# MYO_Ganglion_no_usb.net
KiCad netlist of a schematic drawn in EAGLE
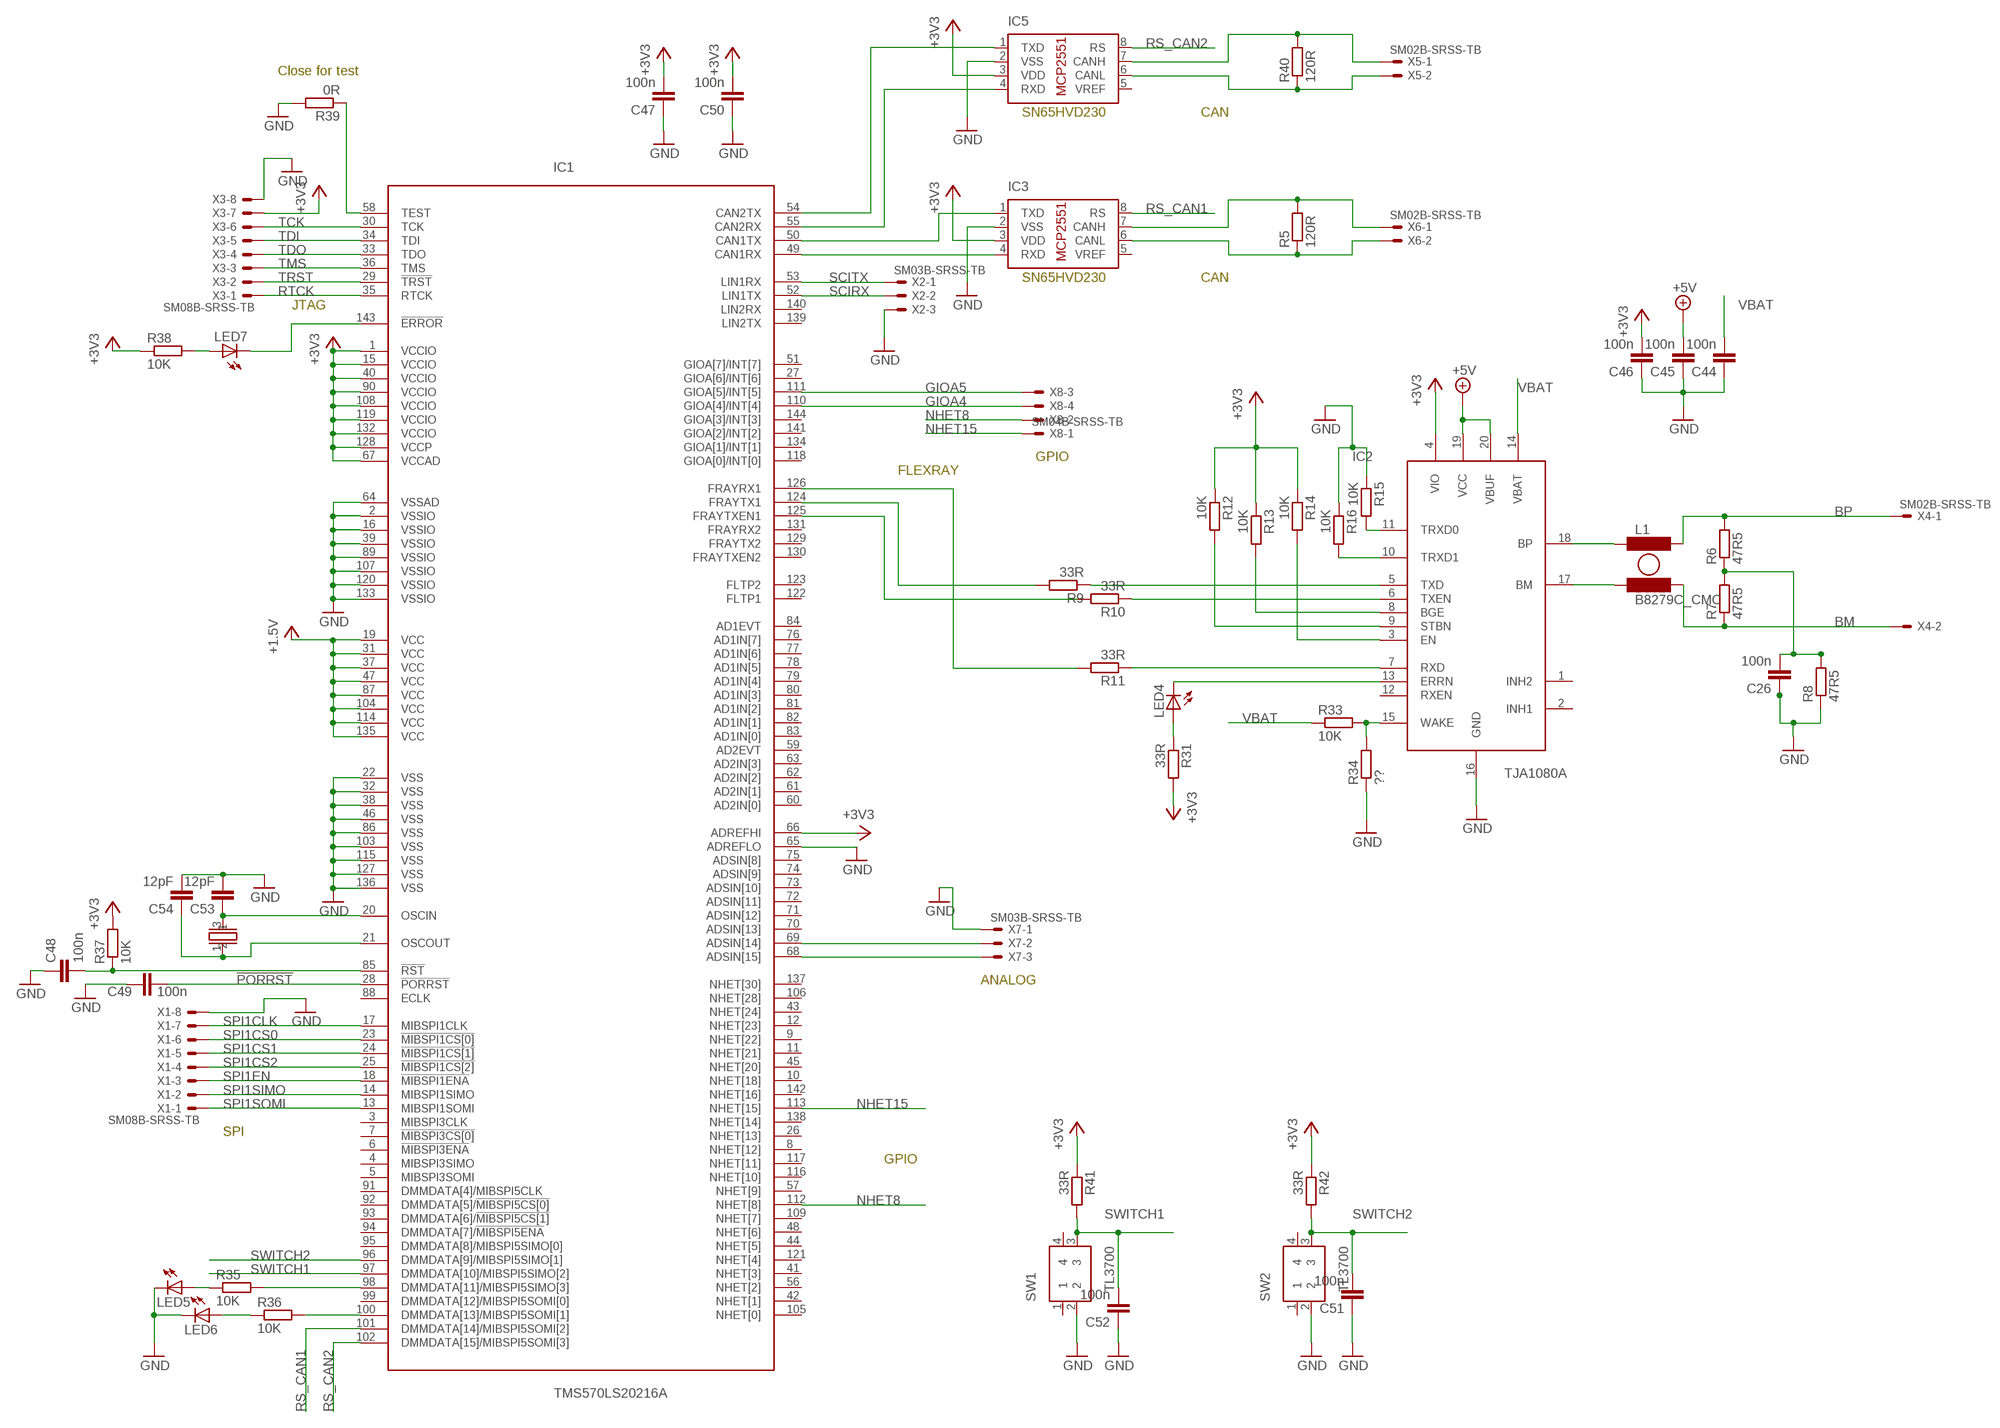
[diagram p0: schematic, sheet 1]
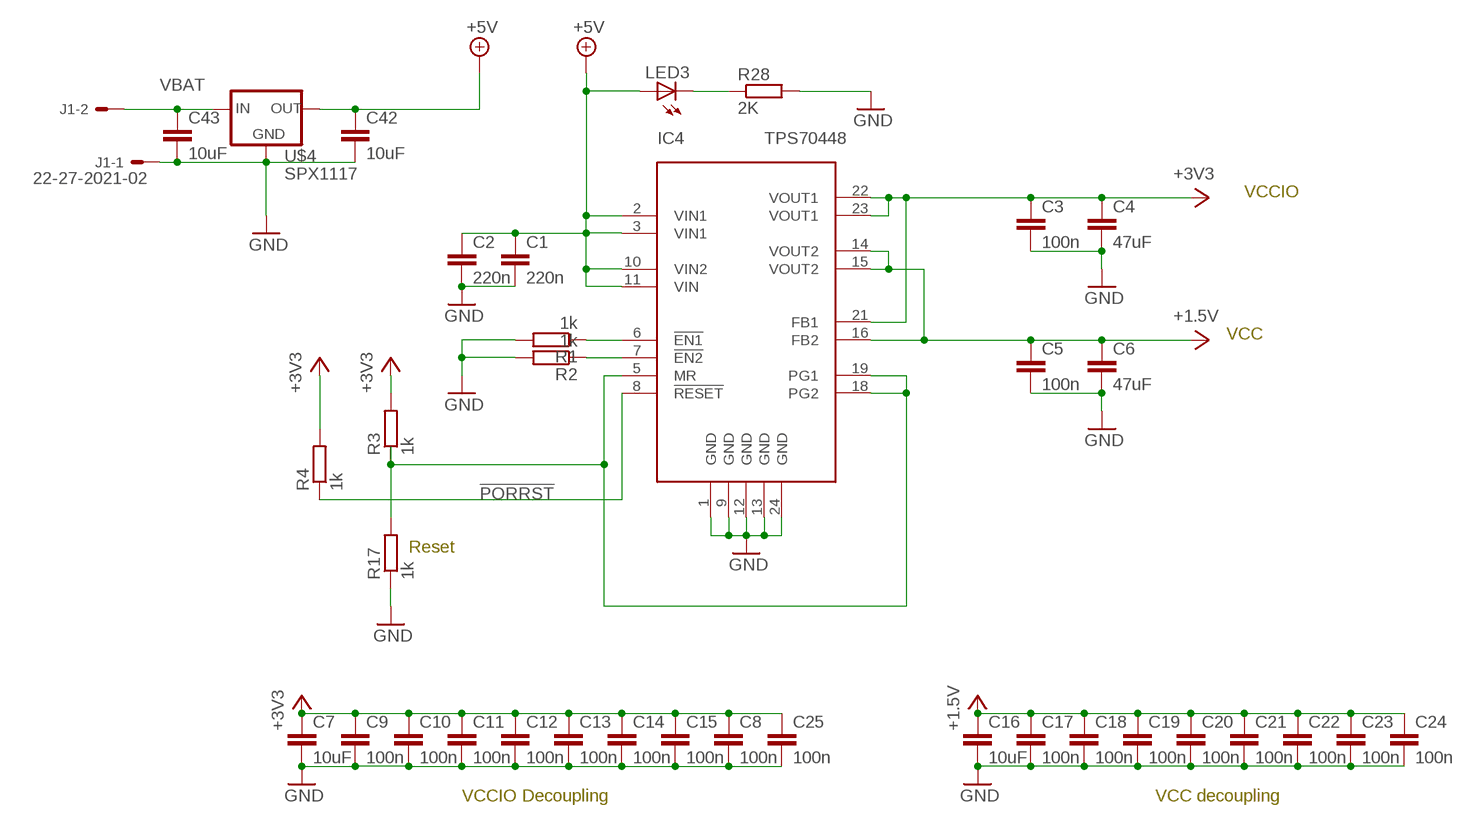
[diagram p1: schematic, sheet 2]

(export (version "E")
  (design (tool "Eeschema 10.0.6"))
  (components
    (comp (ref "C26")
      (value "100n")
      (footprint "eagle-import:C0402K")
      (libsource (lib "eagle-import") (part "C-EUC0402K"))
    )
    (comp (ref "C44")
      (value "100n")
      (footprint "eagle-import:C0402K")
      (libsource (lib "eagle-import") (part "C-EUC0402K"))
    )
    (comp (ref "C45")
      (value "100n")
      (footprint "eagle-import:C0402K")
      (libsource (lib "eagle-import") (part "C-EUC0402K"))
    )
    (comp (ref "C46")
      (value "100n")
      (footprint "eagle-import:C0402K")
      (libsource (lib "eagle-import") (part "C-EUC0402K"))
    )
    (comp (ref "C47")
      (value "100n")
      (footprint "eagle-import:C0402K")
      (libsource (lib "eagle-import") (part "C-EUC0402K"))
    )
    (comp (ref "C48")
      (value "100n")
      (footprint "eagle-import:C0402K")
      (libsource (lib "eagle-import") (part "C-EUC0402K"))
    )
    (comp (ref "C49")
      (value "100n")
      (footprint "eagle-import:C0402K")
      (libsource (lib "eagle-import") (part "C-EUC0402K"))
    )
    (comp (ref "C50")
      (value "100n")
      (footprint "eagle-import:C0402K")
      (libsource (lib "eagle-import") (part "C-EUC0402K"))
    )
    (comp (ref "C51")
      (value "100n")
      (footprint "eagle-import:C0402K")
      (libsource (lib "eagle-import") (part "C-EUC0402K"))
    )
    (comp (ref "C52")
      (value "100n")
      (footprint "eagle-import:C0402K")
      (libsource (lib "eagle-import") (part "C-EUC0402K"))
    )
    (comp (ref "C53")
      (value "12pF")
      (footprint "eagle-import:C0402K")
      (libsource (lib "eagle-import") (part "C-EUC0402K"))
    )
    (comp (ref "C54")
      (value "12pF")
      (footprint "eagle-import:C0402K")
      (libsource (lib "eagle-import") (part "C-EUC0402K"))
    )
    (comp (ref "IC1")
      (value "TMS570LS20216A")
      (footprint "eagle-import:PQFP144")
      (libsource (lib "eagle-import") (part "TMS570LS20216A"))
    )
    (comp (ref "IC2")
      (value "TJA1080A")
      (footprint "eagle-import:TSSOP20")
      (libsource (lib "eagle-import") (part "TJA1080A"))
    )
    (comp (ref "IC3")
      (value "MCP2551/SN")
      (footprint "eagle-import:SO08")
      (libsource (lib "eagle-import") (part "MCP2551/SN"))
    )
    (comp (ref "IC5")
      (value "MCP2551/SN")
      (footprint "eagle-import:SO08")
      (libsource (lib "eagle-import") (part "MCP2551/SN"))
    )
    (comp (ref "L1")
      (value "B8279C_CMC")
      (footprint "eagle-import:1812CMC")
      (libsource (lib "eagle-import") (part "B8279C_CMC"))
    )
    (comp (ref "LED4")
      (value "LEDCHIPLED_0805")
      (footprint "eagle-import:CHIPLED_0805")
      (libsource (lib "eagle-import") (part "LEDCHIPLED_0805"))
    )
    (comp (ref "LED5")
      (value "LEDCHIPLED_0805")
      (footprint "eagle-import:CHIPLED_0805")
      (libsource (lib "eagle-import") (part "LEDCHIPLED_0805"))
    )
    (comp (ref "LED6")
      (value "LEDCHIPLED_0805")
      (footprint "eagle-import:CHIPLED_0805")
      (libsource (lib "eagle-import") (part "LEDCHIPLED_0805"))
    )
    (comp (ref "LED7")
      (value "LEDCHIPLED_0805")
      (footprint "eagle-import:CHIPLED_0805")
      (libsource (lib "eagle-import") (part "LEDCHIPLED_0805"))
    )
    (comp (ref "R5")
      (value "120R")
      (footprint "eagle-import:R0603")
      (libsource (lib "eagle-import") (part "R-EU_R0603"))
    )
    (comp (ref "R6")
      (value "47R5")
      (footprint "eagle-import:R0402")
      (libsource (lib "eagle-import") (part "R-EU_R0402"))
    )
    (comp (ref "R7")
      (value "47R5")
      (footprint "eagle-import:R0402")
      (libsource (lib "eagle-import") (part "R-EU_R0402"))
    )
    (comp (ref "R8")
      (value "47R5")
      (footprint "eagle-import:R0402")
      (libsource (lib "eagle-import") (part "R-EU_R0402"))
    )
    (comp (ref "R9")
      (value "33R")
      (footprint "eagle-import:R0402")
      (libsource (lib "eagle-import") (part "R-EU_R0402"))
    )
    (comp (ref "R10")
      (value "33R")
      (footprint "eagle-import:R0402")
      (libsource (lib "eagle-import") (part "R-EU_R0402"))
    )
    (comp (ref "R11")
      (value "33R")
      (footprint "eagle-import:R0402")
      (libsource (lib "eagle-import") (part "R-EU_R0402"))
    )
    (comp (ref "R12")
      (value "10K")
      (footprint "eagle-import:R0402")
      (libsource (lib "eagle-import") (part "R-EU_R0402"))
    )
    (comp (ref "R13")
      (value "10K")
      (footprint "eagle-import:R0402")
      (libsource (lib "eagle-import") (part "R-EU_R0402"))
    )
    (comp (ref "R14")
      (value "10K")
      (footprint "eagle-import:R0402")
      (libsource (lib "eagle-import") (part "R-EU_R0402"))
    )
    (comp (ref "R15")
      (value "10K")
      (footprint "eagle-import:R0402")
      (libsource (lib "eagle-import") (part "R-EU_R0402"))
    )
    (comp (ref "R16")
      (value "10K")
      (footprint "eagle-import:R0402")
      (libsource (lib "eagle-import") (part "R-EU_R0402"))
    )
    (comp (ref "R31")
      (value "33R")
      (footprint "eagle-import:R0402")
      (libsource (lib "eagle-import") (part "R-EU_R0402"))
    )
    (comp (ref "R33")
      (value "10K")
      (footprint "eagle-import:R0402")
      (libsource (lib "eagle-import") (part "R-EU_R0402"))
    )
    (comp (ref "R34")
      (value "??")
      (footprint "eagle-import:R0402")
      (libsource (lib "eagle-import") (part "R-EU_R0402"))
    )
    (comp (ref "R35")
      (value "10K")
      (footprint "eagle-import:R0402")
      (libsource (lib "eagle-import") (part "R-EU_R0402"))
    )
    (comp (ref "R36")
      (value "10K")
      (footprint "eagle-import:R0402")
      (libsource (lib "eagle-import") (part "R-EU_R0402"))
    )
    (comp (ref "R37")
      (value "10K")
      (footprint "eagle-import:R0402")
      (libsource (lib "eagle-import") (part "R-EU_R0402"))
    )
    (comp (ref "R38")
      (value "10K")
      (footprint "eagle-import:R0402")
      (libsource (lib "eagle-import") (part "R-EU_R0402"))
    )
    (comp (ref "R39")
      (value "0R")
      (footprint "eagle-import:R0402")
      (libsource (lib "eagle-import") (part "R-EU_R0402"))
    )
    (comp (ref "R40")
      (value "120R")
      (footprint "eagle-import:R0603")
      (libsource (lib "eagle-import") (part "R-EU_R0603"))
    )
    (comp (ref "R41")
      (value "33R")
      (footprint "eagle-import:R0402")
      (libsource (lib "eagle-import") (part "R-EU_R0402"))
    )
    (comp (ref "R42")
      (value "33R")
      (footprint "eagle-import:R0402")
      (libsource (lib "eagle-import") (part "R-EU_R0402"))
    )
    (comp (ref "SW1")
      (value "TL3700")
      (footprint "eagle-import:TL3700")
      (libsource (lib "eagle-import") (part "TL3700"))
    )
    (comp (ref "SW2")
      (value "TL3700")
      (footprint "eagle-import:TL3700")
      (libsource (lib "eagle-import") (part "TL3700"))
    )
    (comp (ref "X1")
      (value "SM08B-SRSS-TB")
      (footprint "eagle-import:SM08B-SRSS-TB")
      (libsource (lib "eagle-import") (part "?M08B-SRSS-TBS"))
    )
    (comp (ref "X2")
      (value "SM03B-SRSS-TB")
      (footprint "eagle-import:SM03B-SRSS-TB")
      (libsource (lib "eagle-import") (part "?M03B-SRSS-TBS"))
    )
    (comp (ref "X3")
      (value "SM08B-SRSS-TB")
      (footprint "eagle-import:SM08B-SRSS-TB")
      (libsource (lib "eagle-import") (part "?M08B-SRSS-TBS"))
    )
    (comp (ref "X4")
      (value "SM02B-SRSS-TB")
      (footprint "eagle-import:SM02B-SRSS-TB")
      (libsource (lib "eagle-import") (part "?M02B-SRSS-TBS"))
    )
    (comp (ref "X5")
      (value "SM02B-SRSS-TB")
      (footprint "eagle-import:SM02B-SRSS-TB")
      (libsource (lib "eagle-import") (part "?M02B-SRSS-TBS"))
    )
    (comp (ref "X6")
      (value "SM02B-SRSS-TB")
      (footprint "eagle-import:SM02B-SRSS-TB")
      (libsource (lib "eagle-import") (part "?M02B-SRSS-TBS"))
    )
    (comp (ref "X7")
      (value "SM03B-SRSS-TB")
      (footprint "eagle-import:SM03B-SRSS-TB")
      (libsource (lib "eagle-import") (part "?M03B-SRSS-TBS"))
    )
    (comp (ref "X8")
      (value "SM04B-SRSS-TB")
      (footprint "eagle-import:SM04B-SRSS-TB")
      (libsource (lib "eagle-import") (part "?M04B-SRSS-TBS"))
    )
    (comp (ref "XT1")
      (value "2.5X2_XTAL")
      (footprint "eagle-import:2.5X2_XTAL")
      (libsource (lib "eagle-import") (part "2.5X2_XTAL"))
    )
    (comp (ref "C1")
      (value "220n")
      (footprint "eagle-import:C0402K")
      (libsource (lib "eagle-import") (part "C-EUC0402K"))
    )
    (comp (ref "C2")
      (value "220n")
      (footprint "eagle-import:C0402K")
      (libsource (lib "eagle-import") (part "C-EUC0402K"))
    )
    (comp (ref "C3")
      (value "100n")
      (footprint "eagle-import:C0402K")
      (libsource (lib "eagle-import") (part "C-EUC0402K"))
    )
    (comp (ref "C4")
      (value "47uF")
      (footprint "eagle-import:C0805K")
      (libsource (lib "eagle-import") (part "C-EUC0805K"))
    )
    (comp (ref "C5")
      (value "100n")
      (footprint "eagle-import:C0402K")
      (libsource (lib "eagle-import") (part "C-EUC0402K"))
    )
    (comp (ref "C6")
      (value "47uF")
      (footprint "eagle-import:C0805K")
      (libsource (lib "eagle-import") (part "C-EUC0805K"))
    )
    (comp (ref "C7")
      (value "10uF")
      (footprint "eagle-import:C0805K")
      (libsource (lib "eagle-import") (part "C-EUC0805K"))
    )
    (comp (ref "C8")
      (value "100n")
      (footprint "eagle-import:C0402K")
      (libsource (lib "eagle-import") (part "C-EUC0402K"))
    )
    (comp (ref "C9")
      (value "100n")
      (footprint "eagle-import:C0402K")
      (libsource (lib "eagle-import") (part "C-EUC0402K"))
    )
    (comp (ref "C10")
      (value "100n")
      (footprint "eagle-import:C0402K")
      (libsource (lib "eagle-import") (part "C-EUC0402K"))
    )
    (comp (ref "C11")
      (value "100n")
      (footprint "eagle-import:C0402K")
      (libsource (lib "eagle-import") (part "C-EUC0402K"))
    )
    (comp (ref "C12")
      (value "100n")
      (footprint "eagle-import:C0402K")
      (libsource (lib "eagle-import") (part "C-EUC0402K"))
    )
    (comp (ref "C13")
      (value "100n")
      (footprint "eagle-import:C0402K")
      (libsource (lib "eagle-import") (part "C-EUC0402K"))
    )
    (comp (ref "C14")
      (value "100n")
      (footprint "eagle-import:C0402K")
      (libsource (lib "eagle-import") (part "C-EUC0402K"))
    )
    (comp (ref "C15")
      (value "100n")
      (footprint "eagle-import:C0402K")
      (libsource (lib "eagle-import") (part "C-EUC0402K"))
    )
    (comp (ref "C16")
      (value "10uF")
      (footprint "eagle-import:C0805K")
      (libsource (lib "eagle-import") (part "C-EUC0805K"))
    )
    (comp (ref "C17")
      (value "100n")
      (footprint "eagle-import:C0402K")
      (libsource (lib "eagle-import") (part "C-EUC0402K"))
    )
    (comp (ref "C18")
      (value "100n")
      (footprint "eagle-import:C0402K")
      (libsource (lib "eagle-import") (part "C-EUC0402K"))
    )
    (comp (ref "C19")
      (value "100n")
      (footprint "eagle-import:C0402K")
      (libsource (lib "eagle-import") (part "C-EUC0402K"))
    )
    (comp (ref "C20")
      (value "100n")
      (footprint "eagle-import:C0402K")
      (libsource (lib "eagle-import") (part "C-EUC0402K"))
    )
    (comp (ref "C21")
      (value "100n")
      (footprint "eagle-import:C0402K")
      (libsource (lib "eagle-import") (part "C-EUC0402K"))
    )
    (comp (ref "C22")
      (value "100n")
      (footprint "eagle-import:C0402K")
      (libsource (lib "eagle-import") (part "C-EUC0402K"))
    )
    (comp (ref "C23")
      (value "100n")
      (footprint "eagle-import:C0402K")
      (libsource (lib "eagle-import") (part "C-EUC0402K"))
    )
    (comp (ref "C24")
      (value "100n")
      (footprint "eagle-import:C0402K")
      (libsource (lib "eagle-import") (part "C-EUC0402K"))
    )
    (comp (ref "C25")
      (value "100n")
      (footprint "eagle-import:C0402K")
      (libsource (lib "eagle-import") (part "C-EUC0402K"))
    )
    (comp (ref "C42")
      (value "10uF")
      (footprint "eagle-import:C0805K")
      (libsource (lib "eagle-import") (part "C-EUC0805K"))
    )
    (comp (ref "C43")
      (value "10uF")
      (footprint "eagle-import:C0805K")
      (libsource (lib "eagle-import") (part "C-EUC0805K"))
    )
    (comp (ref "IC4")
      (value "TPS70448")
      (footprint "eagle-import:HTSSOP24PWP")
      (libsource (lib "eagle-import") (part "TPS703XX"))
    )
    (comp (ref "J1")
      (value "22-27-2021-02")
      (footprint "eagle-import:6410-02")
      (libsource (lib "eagle-import") (part "22-?-0227-2021"))
    )
    (comp (ref "LED3")
      (value "LEDCHIPLED_0805")
      (footprint "eagle-import:CHIPLED_0805")
      (libsource (lib "eagle-import") (part "LEDCHIPLED_0805"))
    )
    (comp (ref "R1")
      (value "1k")
      (footprint "eagle-import:R0402")
      (libsource (lib "eagle-import") (part "R-EU_R0402"))
    )
    (comp (ref "R2")
      (value "1k")
      (footprint "eagle-import:R0402")
      (libsource (lib "eagle-import") (part "R-EU_R0402"))
    )
    (comp (ref "R3")
      (value "1k")
      (footprint "eagle-import:R0402")
      (libsource (lib "eagle-import") (part "R-EU_R0402"))
    )
    (comp (ref "R4")
      (value "1k")
      (footprint "eagle-import:R0402")
      (libsource (lib "eagle-import") (part "R-EU_R0402"))
    )
    (comp (ref "R17")
      (value "1k")
      (footprint "eagle-import:R0402")
      (libsource (lib "eagle-import") (part "R-EU_R0402"))
    )
    (comp (ref "R28")
      (value "2K")
      (footprint "eagle-import:R0402")
      (libsource (lib "eagle-import") (part "R-EU_R0402"))
    )
    (comp (ref "U$4")
      (value "SPX1117")
      (footprint "eagle-import:SOT223")
      (libsource (lib "eagle-import") (part "SPX1117"))
    )
  )
  (nets
    (net (code "1") (name "+1V5") (class "Default")
      (node (ref "C16") (pin "1") (pinfunction "1_1") (pintype "passive"))
      (node (ref "C17") (pin "1") (pinfunction "1_1") (pintype "passive"))
      (node (ref "C18") (pin "1") (pinfunction "1_1") (pintype "passive"))
      (node (ref "C19") (pin "1") (pinfunction "1_1") (pintype "passive"))
      (node (ref "C20") (pin "1") (pinfunction "1_1") (pintype "passive"))
      (node (ref "C21") (pin "1") (pinfunction "1_1") (pintype "passive"))
      (node (ref "C22") (pin "1") (pinfunction "1_1") (pintype "passive"))
      (node (ref "C23") (pin "1") (pinfunction "1_1") (pintype "passive"))
      (node (ref "C24") (pin "1") (pinfunction "1_1") (pintype "passive"))
      (node (ref "C5") (pin "1") (pinfunction "1_1") (pintype "passive"))
      (node (ref "C6") (pin "1") (pinfunction "1_1") (pintype "passive"))
      (node (ref "IC1") (pin "104") (pinfunction "VCC_104") (pintype "bidirectional"))
      (node (ref "IC1") (pin "114") (pinfunction "VCC_114") (pintype "bidirectional"))
      (node (ref "IC1") (pin "135") (pinfunction "VCC_135") (pintype "bidirectional"))
      (node (ref "IC1") (pin "19") (pinfunction "VCC_19") (pintype "bidirectional"))
      (node (ref "IC1") (pin "31") (pinfunction "VCC_31") (pintype "bidirectional"))
      (node (ref "IC1") (pin "37") (pinfunction "VCC_37") (pintype "bidirectional"))
      (node (ref "IC1") (pin "47") (pinfunction "VCC_47") (pintype "bidirectional"))
      (node (ref "IC1") (pin "87") (pinfunction "VCC_87") (pintype "bidirectional"))
      (node (ref "IC4") (pin "14") (pinfunction "VOUT2_14") (pintype "power_in"))
      (node (ref "IC4") (pin "15") (pinfunction "VOUT2_15") (pintype "power_in"))
      (node (ref "IC4") (pin "16") (pinfunction "FB2_16") (pintype "bidirectional"))
    )
    (net (code "2") (name "+3V3") (class "Default")
      (node (ref "C10") (pin "1") (pinfunction "1_1") (pintype "passive"))
      (node (ref "C11") (pin "1") (pinfunction "1_1") (pintype "passive"))
      (node (ref "C12") (pin "1") (pinfunction "1_1") (pintype "passive"))
      (node (ref "C13") (pin "1") (pinfunction "1_1") (pintype "passive"))
      (node (ref "C14") (pin "1") (pinfunction "1_1") (pintype "passive"))
      (node (ref "C15") (pin "1") (pinfunction "1_1") (pintype "passive"))
      (node (ref "C25") (pin "1") (pinfunction "1_1") (pintype "passive"))
      (node (ref "C3") (pin "1") (pinfunction "1_1") (pintype "passive"))
      (node (ref "C4") (pin "1") (pinfunction "1_1") (pintype "passive"))
      (node (ref "C46") (pin "2") (pinfunction "2_2") (pintype "passive"))
      (node (ref "C47") (pin "2") (pinfunction "2_2") (pintype "passive"))
      (node (ref "C50") (pin "2") (pinfunction "2_2") (pintype "passive"))
      (node (ref "C7") (pin "1") (pinfunction "1_1") (pintype "passive"))
      (node (ref "C8") (pin "1") (pinfunction "1_1") (pintype "passive"))
      (node (ref "C9") (pin "1") (pinfunction "1_1") (pintype "passive"))
      (node (ref "IC1") (pin "1") (pinfunction "VCCIO_1") (pintype "bidirectional"))
      (node (ref "IC1") (pin "108") (pinfunction "VCCIO_108") (pintype "bidirectional"))
      (node (ref "IC1") (pin "119") (pinfunction "VCCIO_119") (pintype "bidirectional"))
      (node (ref "IC1") (pin "128") (pinfunction "VCCP_128") (pintype "bidirectional"))
      (node (ref "IC1") (pin "132") (pinfunction "VCCIO_132") (pintype "bidirectional"))
      (node (ref "IC1") (pin "15") (pinfunction "VCCIO_15") (pintype "bidirectional"))
      (node (ref "IC1") (pin "40") (pinfunction "VCCIO_40") (pintype "bidirectional"))
      (node (ref "IC1") (pin "66") (pinfunction "ADREFHI_66") (pintype "bidirectional"))
      (node (ref "IC1") (pin "67") (pinfunction "VCCAD_67") (pintype "bidirectional"))
      (node (ref "IC1") (pin "90") (pinfunction "VCCIO_90") (pintype "bidirectional"))
      (node (ref "IC2") (pin "4") (pinfunction "VIO_4") (pintype "bidirectional"))
      (node (ref "IC3") (pin "3") (pinfunction "VDD_3") (pintype "power_in"))
      (node (ref "IC4") (pin "21") (pinfunction "FB1_21") (pintype "bidirectional"))
      (node (ref "IC4") (pin "22") (pinfunction "VOUT1_22") (pintype "power_in"))
      (node (ref "IC4") (pin "23") (pinfunction "VOUT1_23") (pintype "power_in"))
      (node (ref "IC5") (pin "3") (pinfunction "VDD_3") (pintype "power_in"))
      (node (ref "R12") (pin "1") (pinfunction "1_1") (pintype "passive"))
      (node (ref "R13") (pin "1") (pinfunction "1_1") (pintype "passive"))
      (node (ref "R14") (pin "1") (pinfunction "1_1") (pintype "passive"))
      (node (ref "R3") (pin "2") (pinfunction "2_2") (pintype "passive"))
      (node (ref "R31") (pin "2") (pinfunction "2_2") (pintype "passive"))
      (node (ref "R37") (pin "2") (pinfunction "2_2") (pintype "passive"))
      (node (ref "R38") (pin "1") (pinfunction "1_1") (pintype "passive"))
      (node (ref "R4") (pin "2") (pinfunction "2_2") (pintype "passive"))
      (node (ref "R41") (pin "1") (pinfunction "1_1") (pintype "passive"))
      (node (ref "R42") (pin "1") (pinfunction "1_1") (pintype "passive"))
      (node (ref "X3") (pin "7") (pinfunction "S_7") (pintype "passive"))
    )
    (net (code "3") (name "+5V") (class "Default")
      (node (ref "C1") (pin "1") (pinfunction "1_1") (pintype "passive"))
      (node (ref "C2") (pin "1") (pinfunction "1_1") (pintype "passive"))
      (node (ref "C42") (pin "1") (pinfunction "1_1") (pintype "passive"))
      (node (ref "C45") (pin "2") (pinfunction "2_2") (pintype "passive"))
      (node (ref "IC2") (pin "19") (pinfunction "VCC_19") (pintype "bidirectional"))
      (node (ref "IC2") (pin "20") (pinfunction "VBUF_20") (pintype "bidirectional"))
      (node (ref "IC4") (pin "10") (pinfunction "VIN2_10") (pintype "power_in"))
      (node (ref "IC4") (pin "11") (pinfunction "VIN_11") (pintype "power_in"))
      (node (ref "IC4") (pin "2") (pinfunction "VIN1_2") (pintype "power_in"))
      (node (ref "IC4") (pin "3") (pinfunction "VIN1_3") (pintype "power_in"))
      (node (ref "LED3") (pin "A") (pinfunction "A_A") (pintype "passive"))
      (node (ref "U$4") (pin "2") (pinfunction "OUT_2") (pintype "passive"))
    )
    (net (code "4") (name "BM") (class "Default")
      (node (ref "L1") (pin "4") (pinfunction "4_4") (pintype "passive"))
      (node (ref "R7") (pin "1") (pinfunction "1_1") (pintype "passive"))
      (node (ref "X4") (pin "2") (pinfunction "S_2") (pintype "passive"))
    )
    (net (code "5") (name "BP") (class "Default")
      (node (ref "L1") (pin "2") (pinfunction "2_2") (pintype "passive"))
      (node (ref "R6") (pin "2") (pinfunction "2_2") (pintype "passive"))
      (node (ref "X4") (pin "1") (pinfunction "S_1") (pintype "passive"))
    )
    (net (code "6") (name "GIOA4") (class "Default")
      (node (ref "IC1") (pin "110") (pinfunction "GIOA[4]/INT[4]_110") (pintype "bidirectional"))
      (node (ref "X8") (pin "4") (pinfunction "S_4") (pintype "passive"))
    )
    (net (code "7") (name "GIOA5") (class "Default")
      (node (ref "IC1") (pin "111") (pinfunction "GIOA[5]/INT[5]_111") (pintype "bidirectional"))
      (node (ref "X8") (pin "3") (pinfunction "S_3") (pintype "passive"))
    )
    (net (code "8") (name "GND") (class "Default")
      (node (ref "C1") (pin "2") (pinfunction "2_2") (pintype "passive"))
      (node (ref "C10") (pin "2") (pinfunction "2_2") (pintype "passive"))
      (node (ref "C11") (pin "2") (pinfunction "2_2") (pintype "passive"))
      (node (ref "C12") (pin "2") (pinfunction "2_2") (pintype "passive"))
      (node (ref "C13") (pin "2") (pinfunction "2_2") (pintype "passive"))
      (node (ref "C14") (pin "2") (pinfunction "2_2") (pintype "passive"))
      (node (ref "C15") (pin "2") (pinfunction "2_2") (pintype "passive"))
      (node (ref "C16") (pin "2") (pinfunction "2_2") (pintype "passive"))
      (node (ref "C17") (pin "2") (pinfunction "2_2") (pintype "passive"))
      (node (ref "C18") (pin "2") (pinfunction "2_2") (pintype "passive"))
      (node (ref "C19") (pin "2") (pinfunction "2_2") (pintype "passive"))
      (node (ref "C2") (pin "2") (pinfunction "2_2") (pintype "passive"))
      (node (ref "C20") (pin "2") (pinfunction "2_2") (pintype "passive"))
      (node (ref "C21") (pin "2") (pinfunction "2_2") (pintype "passive"))
      (node (ref "C22") (pin "2") (pinfunction "2_2") (pintype "passive"))
      (node (ref "C23") (pin "2") (pinfunction "2_2") (pintype "passive"))
      (node (ref "C24") (pin "2") (pinfunction "2_2") (pintype "passive"))
      (node (ref "C25") (pin "2") (pinfunction "2_2") (pintype "passive"))
      (node (ref "C26") (pin "1") (pinfunction "1_1") (pintype "passive"))
      (node (ref "C3") (pin "2") (pinfunction "2_2") (pintype "passive"))
      (node (ref "C4") (pin "2") (pinfunction "2_2") (pintype "passive"))
      (node (ref "C42") (pin "2") (pinfunction "2_2") (pintype "passive"))
      (node (ref "C43") (pin "2") (pinfunction "2_2") (pintype "passive"))
      (node (ref "C44") (pin "1") (pinfunction "1_1") (pintype "passive"))
      (node (ref "C45") (pin "1") (pinfunction "1_1") (pintype "passive"))
      (node (ref "C46") (pin "1") (pinfunction "1_1") (pintype "passive"))
      (node (ref "C47") (pin "1") (pinfunction "1_1") (pintype "passive"))
      (node (ref "C48") (pin "1") (pinfunction "1_1") (pintype "passive"))
      (node (ref "C49") (pin "1") (pinfunction "1_1") (pintype "passive"))
      (node (ref "C5") (pin "2") (pinfunction "2_2") (pintype "passive"))
      (node (ref "C50") (pin "1") (pinfunction "1_1") (pintype "passive"))
      (node (ref "C51") (pin "1") (pinfunction "1_1") (pintype "passive"))
      (node (ref "C52") (pin "1") (pinfunction "1_1") (pintype "passive"))
      (node (ref "C53") (pin "2") (pinfunction "2_2") (pintype "passive"))
      (node (ref "C54") (pin "2") (pinfunction "2_2") (pintype "passive"))
      (node (ref "C6") (pin "2") (pinfunction "2_2") (pintype "passive"))
      (node (ref "C7") (pin "2") (pinfunction "2_2") (pintype "passive"))
      (node (ref "C8") (pin "2") (pinfunction "2_2") (pintype "passive"))
      (node (ref "C9") (pin "2") (pinfunction "2_2") (pintype "passive"))
      (node (ref "IC1") (pin "103") (pinfunction "VSS_103") (pintype "bidirectional"))
      (node (ref "IC1") (pin "107") (pinfunction "VSSIO_107") (pintype "bidirectional"))
      (node (ref "IC1") (pin "115") (pinfunction "VSS_115") (pintype "bidirectional"))
      (node (ref "IC1") (pin "120") (pinfunction "VSSIO_120") (pintype "bidirectional"))
      (node (ref "IC1") (pin "127") (pinfunction "VSS_127") (pintype "bidirectional"))
      (node (ref "IC1") (pin "133") (pinfunction "VSSIO_133") (pintype "bidirectional"))
      (node (ref "IC1") (pin "136") (pinfunction "VSS_136") (pintype "bidirectional"))
      (node (ref "IC1") (pin "16") (pinfunction "VSSIO_16") (pintype "bidirectional"))
      (node (ref "IC1") (pin "2") (pinfunction "VSSIO_2") (pintype "bidirectional"))
      (node (ref "IC1") (pin "22") (pinfunction "VSS_22") (pintype "bidirectional"))
      (node (ref "IC1") (pin "32") (pinfunction "VSS_32") (pintype "bidirectional"))
      (node (ref "IC1") (pin "38") (pinfunction "VSS_38") (pintype "bidirectional"))
      (node (ref "IC1") (pin "39") (pinfunction "VSSIO_39") (pintype "bidirectional"))
      (node (ref "IC1") (pin "46") (pinfunction "VSS_46") (pintype "bidirectional"))
      (node (ref "IC1") (pin "64") (pinfunction "VSSAD_64") (pintype "bidirectional"))
      (node (ref "IC1") (pin "65") (pinfunction "ADREFLO_65") (pintype "bidirectional"))
      (node (ref "IC1") (pin "86") (pinfunction "VSS_86") (pintype "bidirectional"))
      (node (ref "IC1") (pin "89") (pinfunction "VSSIO_89") (pintype "bidirectional"))
      (node (ref "IC2") (pin "16") (pinfunction "GND_16") (pintype "bidirectional"))
      (node (ref "IC3") (pin "2") (pinfunction "VSS_2") (pintype "power_in"))
      (node (ref "IC4") (pin "1") (pinfunction "GND_1") (pintype "power_in"))
      (node (ref "IC4") (pin "12") (pinfunction "GND_12") (pintype "power_in"))
      (node (ref "IC4") (pin "13") (pinfunction "GND_13") (pintype "power_in"))
      (node (ref "IC4") (pin "24") (pinfunction "GND_24") (pintype "power_in"))
      (node (ref "IC4") (pin "9") (pinfunction "GND_9") (pintype "power_in"))
      (node (ref "IC5") (pin "2") (pinfunction "VSS_2") (pintype "power_in"))
      (node (ref "J1") (pin "1") (pinfunction "S_1") (pintype "passive"))
      (node (ref "LED5") (pin "C") (pinfunction "C_C") (pintype "passive"))
      (node (ref "LED6") (pin "C") (pinfunction "C_C") (pintype "passive"))
      (node (ref "R1") (pin "2") (pinfunction "2_2") (pintype "passive"))
      (node (ref "R15") (pin "1") (pinfunction "1_1") (pintype "passive"))
      (node (ref "R16") (pin "1") (pinfunction "1_1") (pintype "passive"))
      (node (ref "R17") (pin "1") (pinfunction "1_1") (pintype "passive"))
      (node (ref "R2") (pin "2") (pinfunction "2_2") (pintype "passive"))
      (node (ref "R28") (pin "2") (pinfunction "2_2") (pintype "passive"))
      (node (ref "R34") (pin "1") (pinfunction "1_1") (pintype "passive"))
      (node (ref "R39") (pin "2") (pinfunction "2_2") (pintype "passive"))
      (node (ref "R8") (pin "1") (pinfunction "1_1") (pintype "passive"))
      (node (ref "SW1") (pin "2") (pinfunction "2_2") (pintype "bidirectional"))
      (node (ref "SW2") (pin "2") (pinfunction "2_2") (pintype "bidirectional"))
      (node (ref "U$4") (pin "1") (pinfunction "GND_1") (pintype "input"))
      (node (ref "X1") (pin "8") (pinfunction "S_8") (pintype "passive"))
      (node (ref "X2") (pin "3") (pinfunction "S_3") (pintype "passive"))
      (node (ref "X3") (pin "8") (pinfunction "S_8") (pintype "passive"))
      (node (ref "X7") (pin "1") (pinfunction "S_1") (pintype "passive"))
    )
    (net (code "9") (name "NHET8") (class "Default")
      (node (ref "IC1") (pin "112") (pinfunction "NHET[8]_112") (pintype "bidirectional"))
      (node (ref "X8") (pin "2") (pinfunction "S_2") (pintype "passive"))
    )
    (net (code "10") (name "NHET15") (class "Default")
      (node (ref "IC1") (pin "113") (pinfunction "NHET[15]_113") (pintype "bidirectional"))
      (node (ref "X8") (pin "1") (pinfunction "S_1") (pintype "passive"))
    )
    (net (code "11") (name "Net-(C26-Pad2)") (class "Default")
      (node (ref "C26") (pin "2") (pinfunction "2_2") (pintype "passive"))
      (node (ref "R6") (pin "1") (pinfunction "1_1") (pintype "passive"))
      (node (ref "R7") (pin "2") (pinfunction "2_2") (pintype "passive"))
      (node (ref "R8") (pin "2") (pinfunction "2_2") (pintype "passive"))
    )
    (net (code "12") (name "Net-(IC1-ADSIN[14])") (class "Default")
      (node (ref "IC1") (pin "69") (pinfunction "ADSIN[14]_69") (pintype "bidirectional"))
      (node (ref "X7") (pin "2") (pinfunction "S_2") (pintype "passive"))
    )
    (net (code "13") (name "Net-(IC1-ADSIN[15])") (class "Default")
      (node (ref "IC1") (pin "68") (pinfunction "ADSIN[15]_68") (pintype "bidirectional"))
      (node (ref "X7") (pin "3") (pinfunction "S_3") (pintype "passive"))
    )
    (net (code "14") (name "Net-(IC1-CAN1RX)") (class "Default")
      (node (ref "IC1") (pin "49") (pinfunction "CAN1RX_49") (pintype "bidirectional"))
      (node (ref "IC3") (pin "4") (pinfunction "RXD_4") (pintype "output"))
    )
    (net (code "15") (name "Net-(IC1-CAN1TX)") (class "Default")
      (node (ref "IC1") (pin "50") (pinfunction "CAN1TX_50") (pintype "bidirectional"))
      (node (ref "IC3") (pin "1") (pinfunction "TXD_1") (pintype "input"))
    )
    (net (code "16") (name "Net-(IC1-CAN2RX)") (class "Default")
      (node (ref "IC1") (pin "55") (pinfunction "CAN2RX_55") (pintype "bidirectional"))
      (node (ref "IC5") (pin "4") (pinfunction "RXD_4") (pintype "output"))
    )
    (net (code "17") (name "Net-(IC1-CAN2TX)") (class "Default")
      (node (ref "IC1") (pin "54") (pinfunction "CAN2TX_54") (pintype "bidirectional"))
      (node (ref "IC5") (pin "1") (pinfunction "TXD_1") (pintype "input"))
    )
    (net (code "18") (name "Net-(IC1-DMMDATA[11]{slash}MIBSPI5SIMO[3])") (class "Default")
      (node (ref "IC1") (pin "98") (pinfunction "DMMDATA[11]/MIBSPI5SIMO[3]_98") (pintype "bidirectional"))
      (node (ref "R35") (pin "2") (pinfunction "2_2") (pintype "passive"))
    )
    (net (code "19") (name "Net-(IC1-DMMDATA[13]{slash}MIBSPI5SOMI[1])") (class "Default")
      (node (ref "IC1") (pin "100") (pinfunction "DMMDATA[13]/MIBSPI5SOMI[1]_100") (pintype "bidirectional"))
      (node (ref "R36") (pin "2") (pinfunction "2_2") (pintype "passive"))
    )
    (net (code "20") (name "Net-(IC1-FRAYRX1)") (class "Default")
      (node (ref "IC1") (pin "126") (pinfunction "FRAYRX1_126") (pintype "bidirectional"))
      (node (ref "R11") (pin "2") (pinfunction "2_2") (pintype "passive"))
    )
    (net (code "21") (name "Net-(IC1-FRAYTX1)") (class "Default")
      (node (ref "IC1") (pin "124") (pinfunction "FRAYTX1_124") (pintype "bidirectional"))
      (node (ref "R9") (pin "2") (pinfunction "2_2") (pintype "passive"))
    )
    (net (code "22") (name "Net-(IC1-FRAYTXEN1)") (class "Default")
      (node (ref "IC1") (pin "125") (pinfunction "FRAYTXEN1_125") (pintype "bidirectional"))
      (node (ref "R10") (pin "2") (pinfunction "2_2") (pintype "passive"))
    )
    (net (code "23") (name "Net-(IC1-OSCIN)") (class "Default")
      (node (ref "C53") (pin "1") (pinfunction "1_1") (pintype "passive"))
      (node (ref "IC1") (pin "20") (pinfunction "OSCIN_20") (pintype "bidirectional"))
      (node (ref "XT1") (pin "3") (pinfunction "2_3") (pintype "bidirectional"))
    )
    (net (code "24") (name "Net-(IC1-OSCOUT)") (class "Default")
      (node (ref "C54") (pin "1") (pinfunction "1_1") (pintype "passive"))
      (node (ref "IC1") (pin "21") (pinfunction "OSCOUT_21") (pintype "bidirectional"))
      (node (ref "XT1") (pin "1") (pinfunction "1_1") (pintype "bidirectional"))
    )
    (net (code "25") (name "Net-(IC1-TEST)") (class "Default")
      (node (ref "IC1") (pin "58") (pinfunction "TEST_58") (pintype "bidirectional"))
      (node (ref "R39") (pin "1") (pinfunction "1_1") (pintype "passive"))
    )
    (net (code "26") (name "Net-(IC1-~{ERROR})") (class "Default")
      (node (ref "IC1") (pin "143") (pinfunction "~{ERROR}_143") (pintype "bidirectional"))
      (node (ref "LED7") (pin "C") (pinfunction "C_C") (pintype "passive"))
    )
    (net (code "27") (name "Net-(IC1-~{RST})") (class "Default")
      (node (ref "C48") (pin "2") (pinfunction "2_2") (pintype "passive"))
      (node (ref "IC1") (pin "85") (pinfunction "~{RST}_85") (pintype "bidirectional"))
      (node (ref "R37") (pin "1") (pinfunction "1_1") (pintype "passive"))
    )
    (net (code "28") (name "Net-(IC2-BGE)") (class "Default")
      (node (ref "IC2") (pin "8") (pinfunction "BGE_8") (pintype "bidirectional"))
      (node (ref "R13") (pin "2") (pinfunction "2_2") (pintype "passive"))
    )
    (net (code "29") (name "Net-(IC2-BM)") (class "Default")
      (node (ref "IC2") (pin "17") (pinfunction "BM_17") (pintype "bidirectional"))
      (node (ref "L1") (pin "3") (pinfunction "3_3") (pintype "passive"))
    )
    (net (code "30") (name "Net-(IC2-BP)") (class "Default")
      (node (ref "IC2") (pin "18") (pinfunction "BP_18") (pintype "bidirectional"))
      (node (ref "L1") (pin "1") (pinfunction "1_1") (pintype "passive"))
    )
    (net (code "31") (name "Net-(IC2-EN)") (class "Default")
      (node (ref "IC2") (pin "3") (pinfunction "EN_3") (pintype "bidirectional"))
      (node (ref "R14") (pin "2") (pinfunction "2_2") (pintype "passive"))
    )
    (net (code "32") (name "Net-(IC2-ERRN)") (class "Default")
      (node (ref "IC2") (pin "13") (pinfunction "ERRN_13") (pintype "bidirectional"))
      (node (ref "LED4") (pin "C") (pinfunction "C_C") (pintype "passive"))
    )
    (net (code "33") (name "Net-(IC2-RXD)") (class "Default")
      (node (ref "IC2") (pin "7") (pinfunction "RXD_7") (pintype "bidirectional"))
      (node (ref "R11") (pin "1") (pinfunction "1_1") (pintype "passive"))
    )
    (net (code "34") (name "Net-(IC2-STBN)") (class "Default")
      (node (ref "IC2") (pin "9") (pinfunction "STBN_9") (pintype "bidirectional"))
      (node (ref "R12") (pin "2") (pinfunction "2_2") (pintype "passive"))
    )
    (net (code "35") (name "Net-(IC2-TRXD0)") (class "Default")
      (node (ref "IC2") (pin "11") (pinfunction "TRXD0_11") (pintype "bidirectional"))
      (node (ref "R15") (pin "2") (pinfunction "2_2") (pintype "passive"))
    )
    (net (code "36") (name "Net-(IC2-TRXD1)") (class "Default")
      (node (ref "IC2") (pin "10") (pinfunction "TRXD1_10") (pintype "bidirectional"))
      (node (ref "R16") (pin "2") (pinfunction "2_2") (pintype "passive"))
    )
    (net (code "37") (name "Net-(IC2-TXD)") (class "Default")
      (node (ref "IC2") (pin "5") (pinfunction "TXD_5") (pintype "bidirectional"))
      (node (ref "R9") (pin "1") (pinfunction "1_1") (pintype "passive"))
    )
    (net (code "38") (name "Net-(IC2-TXEN)") (class "Default")
      (node (ref "IC2") (pin "6") (pinfunction "TXEN_6") (pintype "bidirectional"))
      (node (ref "R10") (pin "1") (pinfunction "1_1") (pintype "passive"))
    )
    (net (code "39") (name "Net-(IC2-WAKE)") (class "Default")
      (node (ref "IC2") (pin "15") (pinfunction "WAKE_15") (pintype "bidirectional"))
      (node (ref "R33") (pin "2") (pinfunction "2_2") (pintype "passive"))
      (node (ref "R34") (pin "2") (pinfunction "2_2") (pintype "passive"))
    )
    (net (code "40") (name "Net-(IC3-CANH)") (class "Default")
      (node (ref "IC3") (pin "7") (pinfunction "CANH_7") (pintype "bidirectional"))
      (node (ref "R5") (pin "2") (pinfunction "2_2") (pintype "passive"))
      (node (ref "X6") (pin "1") (pinfunction "S_1") (pintype "passive"))
    )
    (net (code "41") (name "Net-(IC3-CANL)") (class "Default")
      (node (ref "IC3") (pin "6") (pinfunction "CANL_6") (pintype "bidirectional"))
      (node (ref "R5") (pin "1") (pinfunction "1_1") (pintype "passive"))
      (node (ref "X6") (pin "2") (pinfunction "S_2") (pintype "passive"))
    )
    (net (code "42") (name "Net-(IC4-MR)") (class "Default")
      (node (ref "IC4") (pin "18") (pinfunction "PG2_18") (pintype "bidirectional"))
      (node (ref "IC4") (pin "19") (pinfunction "PG1_19") (pintype "bidirectional"))
      (node (ref "IC4") (pin "5") (pinfunction "MR_5") (pintype "bidirectional"))
      (node (ref "R17") (pin "2") (pinfunction "2_2") (pintype "passive"))
      (node (ref "R3") (pin "1") (pinfunction "1_1") (pintype "passive"))
    )
    (net (code "43") (name "Net-(IC4-~{EN1})") (class "Default")
      (node (ref "IC4") (pin "6") (pinfunction "~{EN1}_6") (pintype "bidirectional"))
      (node (ref "R1") (pin "1") (pinfunction "1_1") (pintype "passive"))
    )
    (net (code "44") (name "Net-(IC4-~{EN2})") (class "Default")
      (node (ref "IC4") (pin "7") (pinfunction "~{EN2}_7") (pintype "bidirectional"))
      (node (ref "R2") (pin "1") (pinfunction "1_1") (pintype "passive"))
    )
    (net (code "45") (name "Net-(IC5-CANH)") (class "Default")
      (node (ref "IC5") (pin "7") (pinfunction "CANH_7") (pintype "bidirectional"))
      (node (ref "R40") (pin "2") (pinfunction "2_2") (pintype "passive"))
      (node (ref "X5") (pin "1") (pinfunction "S_1") (pintype "passive"))
    )
    (net (code "46") (name "Net-(IC5-CANL)") (class "Default")
      (node (ref "IC5") (pin "6") (pinfunction "CANL_6") (pintype "bidirectional"))
      (node (ref "R40") (pin "1") (pinfunction "1_1") (pintype "passive"))
      (node (ref "X5") (pin "2") (pinfunction "S_2") (pintype "passive"))
    )
    (net (code "47") (name "Net-(LED3-PadC)") (class "Default")
      (node (ref "LED3") (pin "C") (pinfunction "C_C") (pintype "passive"))
      (node (ref "R28") (pin "1") (pinfunction "1_1") (pintype "passive"))
    )
    (net (code "48") (name "Net-(LED4-PadA)") (class "Default")
      (node (ref "LED4") (pin "A") (pinfunction "A_A") (pintype "passive"))
      (node (ref "R31") (pin "1") (pinfunction "1_1") (pintype "passive"))
    )
    (net (code "49") (name "Net-(LED5-PadA)") (class "Default")
      (node (ref "LED5") (pin "A") (pinfunction "A_A") (pintype "passive"))
      (node (ref "R35") (pin "1") (pinfunction "1_1") (pintype "passive"))
    )
    (net (code "50") (name "Net-(LED6-PadA)") (class "Default")
      (node (ref "LED6") (pin "A") (pinfunction "A_A") (pintype "passive"))
      (node (ref "R36") (pin "1") (pinfunction "1_1") (pintype "passive"))
    )
    (net (code "51") (name "Net-(LED7-PadA)") (class "Default")
      (node (ref "LED7") (pin "A") (pinfunction "A_A") (pintype "passive"))
      (node (ref "R38") (pin "2") (pinfunction "2_2") (pintype "passive"))
    )
    (net (code "52") (name "RS_CAN1") (class "Default")
      (node (ref "IC1") (pin "101") (pinfunction "DMMDATA[14]/MIBSPI5SOMI[2]_101") (pintype "bidirectional"))
      (node (ref "IC3") (pin "8") (pinfunction "RS_8") (pintype "input"))
    )
    (net (code "53") (name "RS_CAN2") (class "Default")
      (node (ref "IC1") (pin "102") (pinfunction "DMMDATA[15]/MIBSPI5SOMI[3]_102") (pintype "bidirectional"))
      (node (ref "IC5") (pin "8") (pinfunction "RS_8") (pintype "input"))
    )
    (net (code "54") (name "RTCK") (class "Default")
      (node (ref "IC1") (pin "35") (pinfunction "RTCK_35") (pintype "bidirectional"))
      (node (ref "X3") (pin "1") (pinfunction "S_1") (pintype "passive"))
    )
    (net (code "55") (name "SCIRX") (class "Default")
      (node (ref "IC1") (pin "52") (pinfunction "LIN1TX_52") (pintype "bidirectional"))
      (node (ref "X2") (pin "2") (pinfunction "S_2") (pintype "passive"))
    )
    (net (code "56") (name "SCITX") (class "Default")
      (node (ref "IC1") (pin "53") (pinfunction "LIN1RX_53") (pintype "bidirectional"))
      (node (ref "X2") (pin "1") (pinfunction "S_1") (pintype "passive"))
    )
    (net (code "57") (name "SPI1CLK") (class "Default")
      (node (ref "IC1") (pin "17") (pinfunction "MIBSPI1CLK_17") (pintype "bidirectional"))
      (node (ref "X1") (pin "7") (pinfunction "S_7") (pintype "passive"))
    )
    (net (code "58") (name "SPI1CS0") (class "Default")
      (node (ref "IC1") (pin "23") (pinfunction "~{MIBSPI1CS[0]}_23") (pintype "bidirectional"))
      (node (ref "X1") (pin "6") (pinfunction "S_6") (pintype "passive"))
    )
    (net (code "59") (name "SPI1CS1") (class "Default")
      (node (ref "IC1") (pin "24") (pinfunction "~{MIBSPI1CS[1]}_24") (pintype "bidirectional"))
      (node (ref "X1") (pin "5") (pinfunction "S_5") (pintype "passive"))
    )
    (net (code "60") (name "SPI1CS2") (class "Default")
      (node (ref "IC1") (pin "25") (pinfunction "~{MIBSPI1CS[2]}_25") (pintype "bidirectional"))
      (node (ref "X1") (pin "4") (pinfunction "S_4") (pintype "passive"))
    )
    (net (code "61") (name "SPI1EN") (class "Default")
      (node (ref "IC1") (pin "18") (pinfunction "~{MIBSPI1ENA}_18") (pintype "bidirectional"))
      (node (ref "X1") (pin "3") (pinfunction "S_3") (pintype "passive"))
    )
    (net (code "62") (name "SPI1SIMO") (class "Default")
      (node (ref "IC1") (pin "14") (pinfunction "MIBSPI1SIMO_14") (pintype "bidirectional"))
      (node (ref "X1") (pin "2") (pinfunction "S_2") (pintype "passive"))
    )
    (net (code "63") (name "SPI1SOMI") (class "Default")
      (node (ref "IC1") (pin "13") (pinfunction "MIBSPI1SOMI_13") (pintype "bidirectional"))
      (node (ref "X1") (pin "1") (pinfunction "S_1") (pintype "passive"))
    )
    (net (code "64") (name "SWITCH1") (class "Default")
      (node (ref "C52") (pin "2") (pinfunction "2_2") (pintype "passive"))
      (node (ref "IC1") (pin "97") (pinfunction "DMMDATA[10]/MIBSPI5SIMO[2]_97") (pintype "bidirectional"))
      (node (ref "R41") (pin "2") (pinfunction "2_2") (pintype "passive"))
      (node (ref "SW1") (pin "3") (pinfunction "3_3") (pintype "bidirectional"))
    )
    (net (code "65") (name "SWITCH2") (class "Default")
      (node (ref "C51") (pin "2") (pinfunction "2_2") (pintype "passive"))
      (node (ref "IC1") (pin "96") (pinfunction "DMMDATA[9]/MIBSPI5SIMO[1]_96") (pintype "bidirectional"))
      (node (ref "R42") (pin "2") (pinfunction "2_2") (pintype "passive"))
      (node (ref "SW2") (pin "3") (pinfunction "3_3") (pintype "bidirectional"))
    )
    (net (code "66") (name "TCK") (class "Default")
      (node (ref "IC1") (pin "30") (pinfunction "TCK_30") (pintype "bidirectional"))
      (node (ref "X3") (pin "6") (pinfunction "S_6") (pintype "passive"))
    )
    (net (code "67") (name "TDI") (class "Default")
      (node (ref "IC1") (pin "34") (pinfunction "TDI_34") (pintype "bidirectional"))
      (node (ref "X3") (pin "5") (pinfunction "S_5") (pintype "passive"))
    )
    (net (code "68") (name "TDO") (class "Default")
      (node (ref "IC1") (pin "33") (pinfunction "TDO_33") (pintype "bidirectional"))
      (node (ref "X3") (pin "4") (pinfunction "S_4") (pintype "passive"))
    )
    (net (code "69") (name "TMS") (class "Default")
      (node (ref "IC1") (pin "36") (pinfunction "TMS_36") (pintype "bidirectional"))
      (node (ref "X3") (pin "3") (pinfunction "S_3") (pintype "passive"))
    )
    (net (code "70") (name "TRST") (class "Default")
      (node (ref "IC1") (pin "29") (pinfunction "~{TRST}_29") (pintype "bidirectional"))
      (node (ref "X3") (pin "2") (pinfunction "S_2") (pintype "passive"))
    )
    (net (code "71") (name "VBAT") (class "Default")
      (node (ref "C43") (pin "1") (pinfunction "1_1") (pintype "passive"))
      (node (ref "C44") (pin "2") (pinfunction "2_2") (pintype "passive"))
      (node (ref "IC2") (pin "14") (pinfunction "VBAT_14") (pintype "bidirectional"))
      (node (ref "J1") (pin "2") (pinfunction "S_2") (pintype "passive"))
      (node (ref "R33") (pin "1") (pinfunction "1_1") (pintype "passive"))
      (node (ref "U$4") (pin "3") (pinfunction "IN_3") (pintype "input"))
    )
    (net (code "72") (name "unconnected-(IC1-AD1EVT-Pad84)") (class "Default")
      (node (ref "IC1") (pin "84") (pinfunction "AD1EVT_84") (pintype "bidirectional"))
    )
    (net (code "73") (name "unconnected-(IC1-AD1IN[0]-Pad83)") (class "Default")
      (node (ref "IC1") (pin "83") (pinfunction "AD1IN[0]_83") (pintype "bidirectional"))
    )
    (net (code "74") (name "unconnected-(IC1-AD1IN[1]-Pad82)") (class "Default")
      (node (ref "IC1") (pin "82") (pinfunction "AD1IN[1]_82") (pintype "bidirectional"))
    )
    (net (code "75") (name "unconnected-(IC1-AD1IN[2]-Pad81)") (class "Default")
      (node (ref "IC1") (pin "81") (pinfunction "AD1IN[2]_81") (pintype "bidirectional"))
    )
    (net (code "76") (name "unconnected-(IC1-AD1IN[3]-Pad80)") (class "Default")
      (node (ref "IC1") (pin "80") (pinfunction "AD1IN[3]_80") (pintype "bidirectional"))
    )
    (net (code "77") (name "unconnected-(IC1-AD1IN[4]-Pad79)") (class "Default")
      (node (ref "IC1") (pin "79") (pinfunction "AD1IN[4]_79") (pintype "bidirectional"))
    )
    (net (code "78") (name "unconnected-(IC1-AD1IN[5]-Pad78)") (class "Default")
      (node (ref "IC1") (pin "78") (pinfunction "AD1IN[5]_78") (pintype "bidirectional"))
    )
    (net (code "79") (name "unconnected-(IC1-AD1IN[6]-Pad77)") (class "Default")
      (node (ref "IC1") (pin "77") (pinfunction "AD1IN[6]_77") (pintype "bidirectional"))
    )
    (net (code "80") (name "unconnected-(IC1-AD1IN[7]-Pad76)") (class "Default")
      (node (ref "IC1") (pin "76") (pinfunction "AD1IN[7]_76") (pintype "bidirectional"))
    )
    (net (code "81") (name "unconnected-(IC1-AD2EVT-Pad59)") (class "Default")
      (node (ref "IC1") (pin "59") (pinfunction "AD2EVT_59") (pintype "bidirectional"))
    )
    (net (code "82") (name "unconnected-(IC1-AD2IN[0]-Pad60)") (class "Default")
      (node (ref "IC1") (pin "60") (pinfunction "AD2IN[0]_60") (pintype "bidirectional"))
    )
    (net (code "83") (name "unconnected-(IC1-AD2IN[1]-Pad61)") (class "Default")
      (node (ref "IC1") (pin "61") (pinfunction "AD2IN[1]_61") (pintype "bidirectional"))
    )
    (net (code "84") (name "unconnected-(IC1-AD2IN[2]-Pad62)") (class "Default")
      (node (ref "IC1") (pin "62") (pinfunction "AD2IN[2]_62") (pintype "bidirectional"))
    )
    (net (code "85") (name "unconnected-(IC1-AD2IN[3]-Pad63)") (class "Default")
      (node (ref "IC1") (pin "63") (pinfunction "AD2IN[3]_63") (pintype "bidirectional"))
    )
    (net (code "86") (name "unconnected-(IC1-ADSIN[8]-Pad75)") (class "Default")
      (node (ref "IC1") (pin "75") (pinfunction "ADSIN[8]_75") (pintype "bidirectional"))
    )
    (net (code "87") (name "unconnected-(IC1-ADSIN[9]-Pad74)") (class "Default")
      (node (ref "IC1") (pin "74") (pinfunction "ADSIN[9]_74") (pintype "bidirectional"))
    )
    (net (code "88") (name "unconnected-(IC1-ADSIN[10]-Pad73)") (class "Default")
      (node (ref "IC1") (pin "73") (pinfunction "ADSIN[10]_73") (pintype "bidirectional"))
    )
    (net (code "89") (name "unconnected-(IC1-ADSIN[11]-Pad72)") (class "Default")
      (node (ref "IC1") (pin "72") (pinfunction "ADSIN[11]_72") (pintype "bidirectional"))
    )
    (net (code "90") (name "unconnected-(IC1-ADSIN[12]-Pad71)") (class "Default")
      (node (ref "IC1") (pin "71") (pinfunction "ADSIN[12]_71") (pintype "bidirectional"))
    )
    (net (code "91") (name "unconnected-(IC1-ADSIN[13]-Pad70)") (class "Default")
      (node (ref "IC1") (pin "70") (pinfunction "ADSIN[13]_70") (pintype "bidirectional"))
    )
    (net (code "92") (name "unconnected-(IC1-DMMDATA[4]{slash}MIBSPI5CLK-Pad91)") (class "Default")
      (node (ref "IC1") (pin "91") (pinfunction "DMMDATA[4]/MIBSPI5CLK_91") (pintype "bidirectional"))
    )
    (net (code "93") (name "unconnected-(IC1-DMMDATA[5]{slash}~{MIBSPI5CS[0]}-Pad92)") (class "Default")
      (node (ref "IC1") (pin "92") (pinfunction "DMMDATA[5]/~{MIBSPI5CS[0]}_92") (pintype "bidirectional"))
    )
    (net (code "94") (name "unconnected-(IC1-DMMDATA[6]{slash}~{MIBSPI5CS[1]}-Pad93)") (class "Default")
      (node (ref "IC1") (pin "93") (pinfunction "DMMDATA[6]/~{MIBSPI5CS[1]}_93") (pintype "bidirectional"))
    )
    (net (code "95") (name "unconnected-(IC1-DMMDATA[7]{slash}~{MIBSPI5ENA}-Pad94)") (class "Default")
      (node (ref "IC1") (pin "94") (pinfunction "DMMDATA[7]/~{MIBSPI5ENA}_94") (pintype "bidirectional"))
    )
    (net (code "96") (name "unconnected-(IC1-DMMDATA[8]{slash}MIBSPI5SIMO[0]-Pad95)") (class "Default")
      (node (ref "IC1") (pin "95") (pinfunction "DMMDATA[8]/MIBSPI5SIMO[0]_95") (pintype "bidirectional"))
    )
    (net (code "97") (name "unconnected-(IC1-DMMDATA[12]{slash}MIBSPI5SOMI[0]-Pad99)") (class "Default")
      (node (ref "IC1") (pin "99") (pinfunction "DMMDATA[12]/MIBSPI5SOMI[0]_99") (pintype "bidirectional"))
    )
    (net (code "98") (name "unconnected-(IC1-ECLK-Pad88)") (class "Default")
      (node (ref "IC1") (pin "88") (pinfunction "ECLK_88") (pintype "bidirectional"))
    )
    (net (code "99") (name "unconnected-(IC1-FLTP1-Pad122)") (class "Default")
      (node (ref "IC1") (pin "122") (pinfunction "FLTP1_122") (pintype "bidirectional"))
    )
    (net (code "100") (name "unconnected-(IC1-FLTP2-Pad123)") (class "Default")
      (node (ref "IC1") (pin "123") (pinfunction "FLTP2_123") (pintype "bidirectional"))
    )
    (net (code "101") (name "unconnected-(IC1-FRAYRX2-Pad131)") (class "Default")
      (node (ref "IC1") (pin "131") (pinfunction "FRAYRX2_131") (pintype "bidirectional"))
    )
    (net (code "102") (name "unconnected-(IC1-FRAYTX2-Pad129)") (class "Default")
      (node (ref "IC1") (pin "129") (pinfunction "FRAYTX2_129") (pintype "bidirectional"))
    )
    (net (code "103") (name "unconnected-(IC1-FRAYTXEN2-Pad130)") (class "Default")
      (node (ref "IC1") (pin "130") (pinfunction "FRAYTXEN2_130") (pintype "bidirectional"))
    )
    (net (code "104") (name "unconnected-(IC1-GIOA[0]{slash}INT[0]-Pad118)") (class "Default")
      (node (ref "IC1") (pin "118") (pinfunction "GIOA[0]/INT[0]_118") (pintype "bidirectional"))
    )
    (net (code "105") (name "unconnected-(IC1-GIOA[1]{slash}INT[1]-Pad134)") (class "Default")
      (node (ref "IC1") (pin "134") (pinfunction "GIOA[1]/INT[1]_134") (pintype "bidirectional"))
    )
    (net (code "106") (name "unconnected-(IC1-GIOA[2]{slash}INT[2]-Pad141)") (class "Default")
      (node (ref "IC1") (pin "141") (pinfunction "GIOA[2]/INT[2]_141") (pintype "bidirectional"))
    )
    (net (code "107") (name "unconnected-(IC1-GIOA[3]{slash}INT[3]-Pad144)") (class "Default")
      (node (ref "IC1") (pin "144") (pinfunction "GIOA[3]/INT[3]_144") (pintype "bidirectional"))
    )
    (net (code "108") (name "unconnected-(IC1-GIOA[6]{slash}INT[6]-Pad27)") (class "Default")
      (node (ref "IC1") (pin "27") (pinfunction "GIOA[6]/INT[6]_27") (pintype "bidirectional"))
    )
    (net (code "109") (name "unconnected-(IC1-GIOA[7]{slash}INT[7]-Pad51)") (class "Default")
      (node (ref "IC1") (pin "51") (pinfunction "GIOA[7]/INT[7]_51") (pintype "bidirectional"))
    )
    (net (code "110") (name "unconnected-(IC1-LIN2RX-Pad140)") (class "Default")
      (node (ref "IC1") (pin "140") (pinfunction "LIN2RX_140") (pintype "bidirectional"))
    )
    (net (code "111") (name "unconnected-(IC1-LIN2TX-Pad139)") (class "Default")
      (node (ref "IC1") (pin "139") (pinfunction "LIN2TX_139") (pintype "bidirectional"))
    )
    (net (code "112") (name "unconnected-(IC1-MIBSPI3CLK-Pad3)") (class "Default")
      (node (ref "IC1") (pin "3") (pinfunction "MIBSPI3CLK_3") (pintype "bidirectional"))
    )
    (net (code "113") (name "unconnected-(IC1-MIBSPI3SIMO-Pad4)") (class "Default")
      (node (ref "IC1") (pin "4") (pinfunction "MIBSPI3SIMO_4") (pintype "bidirectional"))
    )
    (net (code "114") (name "unconnected-(IC1-MIBSPI3SOMI-Pad5)") (class "Default")
      (node (ref "IC1") (pin "5") (pinfunction "MIBSPI3SOMI_5") (pintype "bidirectional"))
    )
    (net (code "115") (name "unconnected-(IC1-NHET[0]-Pad105)") (class "Default")
      (node (ref "IC1") (pin "105") (pinfunction "NHET[0]_105") (pintype "bidirectional"))
    )
    (net (code "116") (name "unconnected-(IC1-NHET[1]-Pad42)") (class "Default")
      (node (ref "IC1") (pin "42") (pinfunction "NHET[1]_42") (pintype "bidirectional"))
    )
    (net (code "117") (name "unconnected-(IC1-NHET[2]-Pad56)") (class "Default")
      (node (ref "IC1") (pin "56") (pinfunction "NHET[2]_56") (pintype "bidirectional"))
    )
    (net (code "118") (name "unconnected-(IC1-NHET[3]-Pad41)") (class "Default")
      (node (ref "IC1") (pin "41") (pinfunction "NHET[3]_41") (pintype "bidirectional"))
    )
    (net (code "119") (name "unconnected-(IC1-NHET[4]-Pad121)") (class "Default")
      (node (ref "IC1") (pin "121") (pinfunction "NHET[4]_121") (pintype "bidirectional"))
    )
    (net (code "120") (name "unconnected-(IC1-NHET[5]-Pad44)") (class "Default")
      (node (ref "IC1") (pin "44") (pinfunction "NHET[5]_44") (pintype "bidirectional"))
    )
    (net (code "121") (name "unconnected-(IC1-NHET[6]-Pad48)") (class "Default")
      (node (ref "IC1") (pin "48") (pinfunction "NHET[6]_48") (pintype "bidirectional"))
    )
    (net (code "122") (name "unconnected-(IC1-NHET[7]-Pad109)") (class "Default")
      (node (ref "IC1") (pin "109") (pinfunction "NHET[7]_109") (pintype "bidirectional"))
    )
    (net (code "123") (name "unconnected-(IC1-NHET[9]-Pad57)") (class "Default")
      (node (ref "IC1") (pin "57") (pinfunction "NHET[9]_57") (pintype "bidirectional"))
    )
    (net (code "124") (name "unconnected-(IC1-NHET[10]-Pad116)") (class "Default")
      (node (ref "IC1") (pin "116") (pinfunction "NHET[10]_116") (pintype "bidirectional"))
    )
    (net (code "125") (name "unconnected-(IC1-NHET[11]-Pad117)") (class "Default")
      (node (ref "IC1") (pin "117") (pinfunction "NHET[11]_117") (pintype "bidirectional"))
    )
    (net (code "126") (name "unconnected-(IC1-NHET[12]-Pad8)") (class "Default")
      (node (ref "IC1") (pin "8") (pinfunction "NHET[12]_8") (pintype "bidirectional"))
    )
    (net (code "127") (name "unconnected-(IC1-NHET[13]-Pad26)") (class "Default")
      (node (ref "IC1") (pin "26") (pinfunction "NHET[13]_26") (pintype "bidirectional"))
    )
    (net (code "128") (name "unconnected-(IC1-NHET[14]-Pad138)") (class "Default")
      (node (ref "IC1") (pin "138") (pinfunction "NHET[14]_138") (pintype "bidirectional"))
    )
    (net (code "129") (name "unconnected-(IC1-NHET[16]-Pad142)") (class "Default")
      (node (ref "IC1") (pin "142") (pinfunction "NHET[16]_142") (pintype "bidirectional"))
    )
    (net (code "130") (name "unconnected-(IC1-NHET[18]-Pad10)") (class "Default")
      (node (ref "IC1") (pin "10") (pinfunction "NHET[18]_10") (pintype "bidirectional"))
    )
    (net (code "131") (name "unconnected-(IC1-NHET[20]-Pad45)") (class "Default")
      (node (ref "IC1") (pin "45") (pinfunction "NHET[20]_45") (pintype "bidirectional"))
    )
    (net (code "132") (name "unconnected-(IC1-NHET[21]-Pad11)") (class "Default")
      (node (ref "IC1") (pin "11") (pinfunction "NHET[21]_11") (pintype "bidirectional"))
    )
    (net (code "133") (name "unconnected-(IC1-NHET[22]-Pad9)") (class "Default")
      (node (ref "IC1") (pin "9") (pinfunction "NHET[22]_9") (pintype "bidirectional"))
    )
    (net (code "134") (name "unconnected-(IC1-NHET[23]-Pad12)") (class "Default")
      (node (ref "IC1") (pin "12") (pinfunction "NHET[23]_12") (pintype "bidirectional"))
    )
    (net (code "135") (name "unconnected-(IC1-NHET[24]-Pad43)") (class "Default")
      (node (ref "IC1") (pin "43") (pinfunction "NHET[24]_43") (pintype "bidirectional"))
    )
    (net (code "136") (name "unconnected-(IC1-NHET[28]-Pad106)") (class "Default")
      (node (ref "IC1") (pin "106") (pinfunction "NHET[28]_106") (pintype "bidirectional"))
    )
    (net (code "137") (name "unconnected-(IC1-NHET[30]-Pad137)") (class "Default")
      (node (ref "IC1") (pin "137") (pinfunction "NHET[30]_137") (pintype "bidirectional"))
    )
    (net (code "138") (name "unconnected-(IC1-~{MIBSPI3CS[0]}-Pad7)") (class "Default")
      (node (ref "IC1") (pin "7") (pinfunction "~{MIBSPI3CS[0]}_7") (pintype "bidirectional"))
    )
    (net (code "139") (name "unconnected-(IC1-~{MIBSPI3ENA}-Pad6)") (class "Default")
      (node (ref "IC1") (pin "6") (pinfunction "~{MIBSPI3ENA}_6") (pintype "bidirectional"))
    )
    (net (code "140") (name "unconnected-(IC2-INH1-Pad2)") (class "Default")
      (node (ref "IC2") (pin "2") (pinfunction "INH1_2") (pintype "bidirectional"))
    )
    (net (code "141") (name "unconnected-(IC2-INH2-Pad1)") (class "Default")
      (node (ref "IC2") (pin "1") (pinfunction "INH2_1") (pintype "bidirectional"))
    )
    (net (code "142") (name "unconnected-(IC2-RXEN-Pad12)") (class "Default")
      (node (ref "IC2") (pin "12") (pinfunction "RXEN_12") (pintype "bidirectional"))
    )
    (net (code "143") (name "unconnected-(IC3-VREF-Pad5)") (class "Default")
      (node (ref "IC3") (pin "5") (pinfunction "VREF_5") (pintype "output"))
    )
    (net (code "144") (name "unconnected-(IC5-VREF-Pad5)") (class "Default")
      (node (ref "IC5") (pin "5") (pinfunction "VREF_5") (pintype "output"))
    )
    (net (code "145") (name "unconnected-(SW1-Pad1)") (class "Default")
      (node (ref "SW1") (pin "1") (pinfunction "1_1") (pintype "bidirectional"))
    )
    (net (code "146") (name "unconnected-(SW1-Pad4)") (class "Default")
      (node (ref "SW1") (pin "4") (pinfunction "4_4") (pintype "bidirectional"))
    )
    (net (code "147") (name "unconnected-(SW2-Pad1)") (class "Default")
      (node (ref "SW2") (pin "1") (pinfunction "1_1") (pintype "bidirectional"))
    )
    (net (code "148") (name "unconnected-(SW2-Pad4)") (class "Default")
      (node (ref "SW2") (pin "4") (pinfunction "4_4") (pintype "bidirectional"))
    )
    (net (code "149") (name "~{PORRST}") (class "Default")
      (node (ref "C49") (pin "2") (pinfunction "2_2") (pintype "passive"))
      (node (ref "IC1") (pin "28") (pinfunction "~{PORRST}_28") (pintype "bidirectional"))
      (node (ref "IC4") (pin "8") (pinfunction "~{RESET}_8") (pintype "bidirectional"))
      (node (ref "R4") (pin "1") (pinfunction "1_1") (pintype "passive"))
    )
  )
)
